# 08-1G_Phy2.net
KiCad netlist of a schematic drawn in Altium Designer
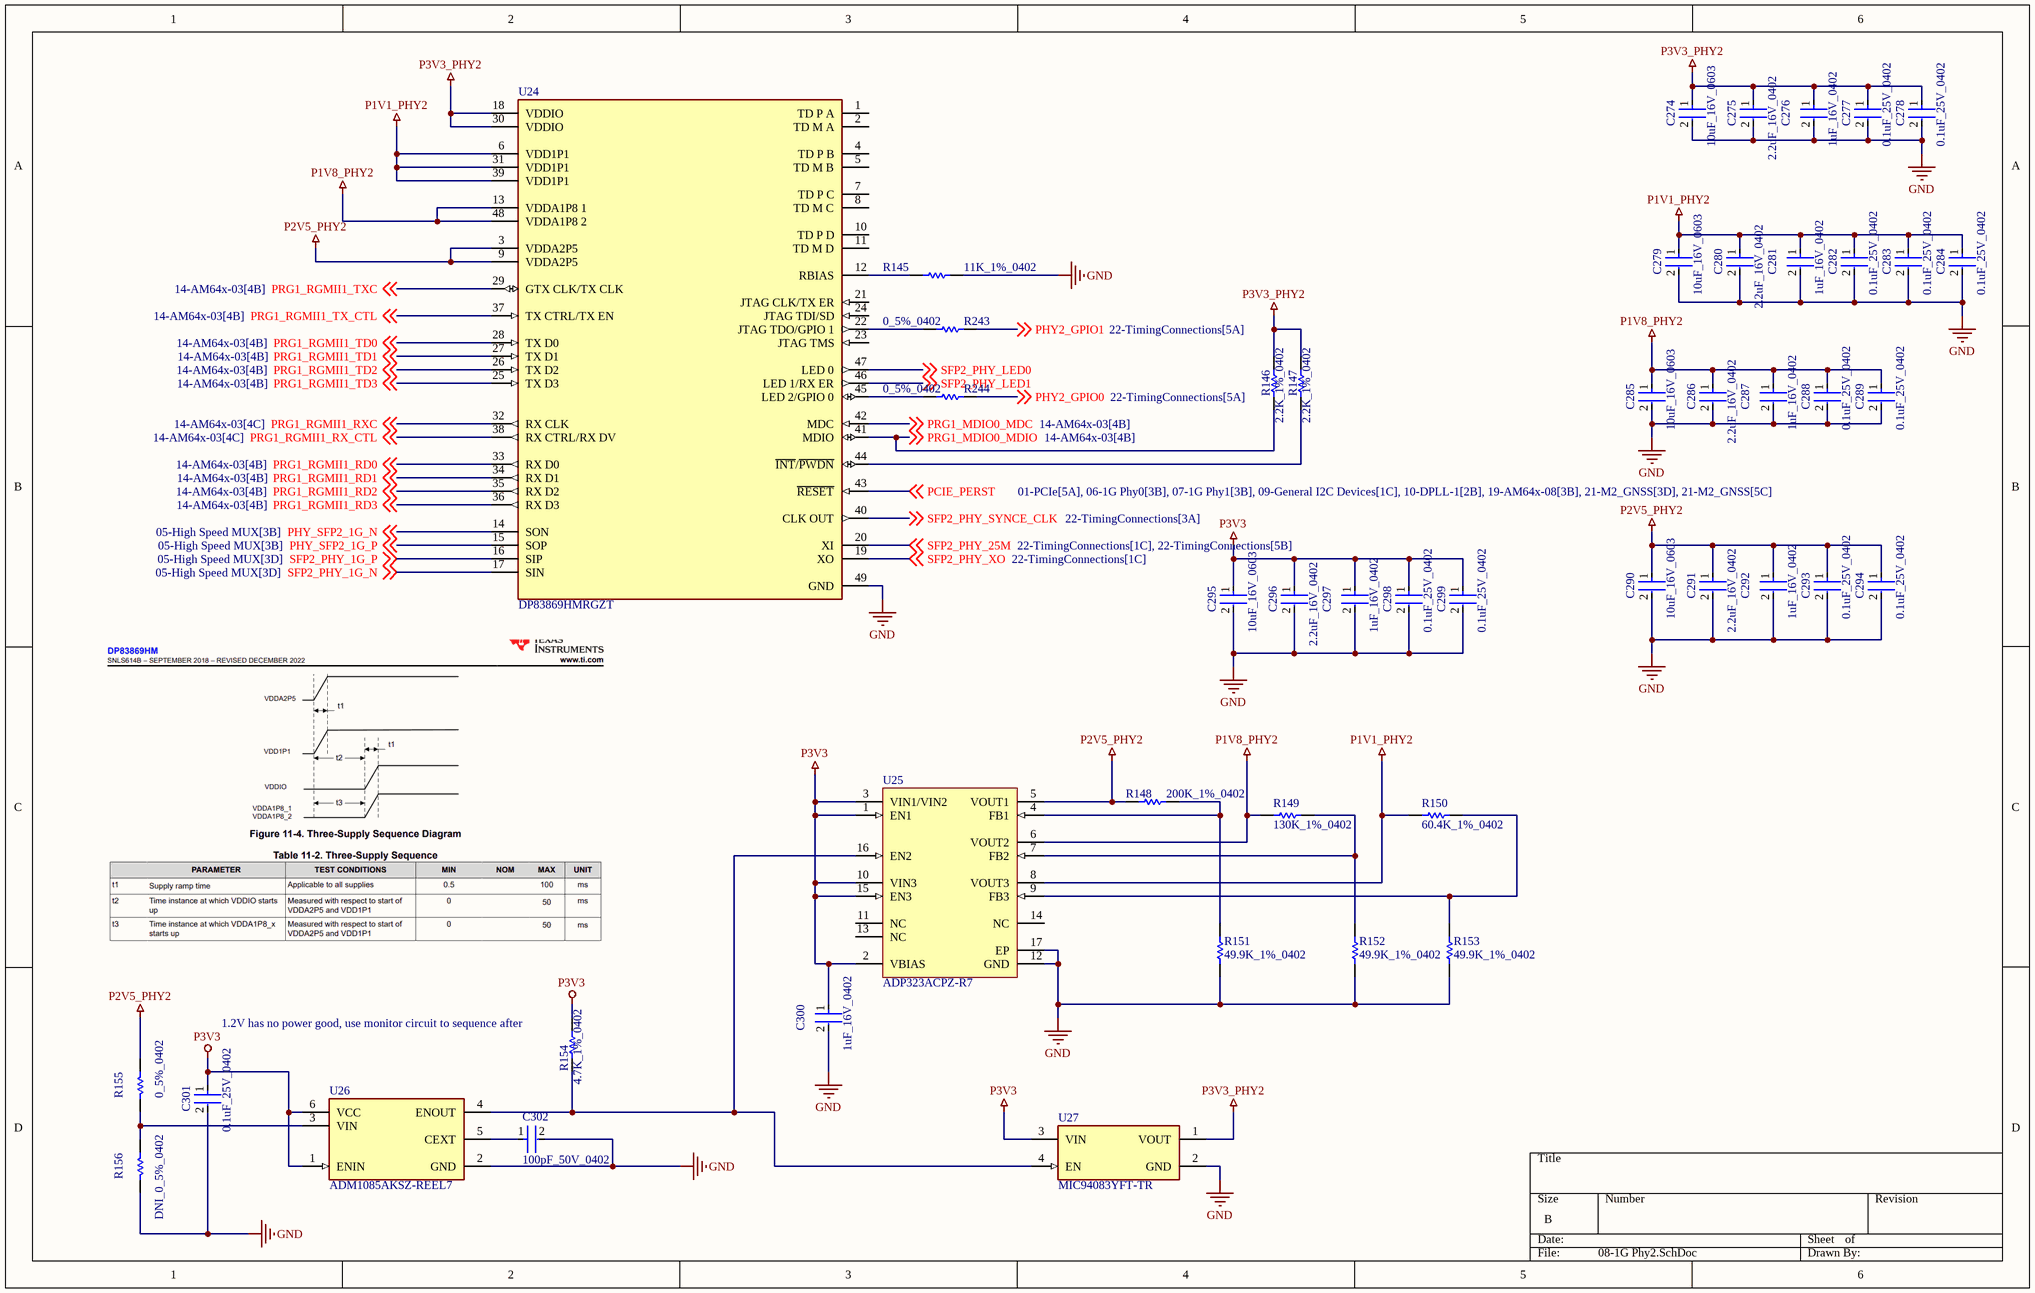
[diagram p0: 08-1G Phy2.SchDoc]

(export (version "E")
  (design (tool "Eeschema 10.0.6"))
  (components
    (comp (ref "C274")
      (value "10uF_16V_0603")
      (footprint "FP-0603-L_1_6_0_2-W_0_8_0-MFG")
      (description "Multilayer Ceramic Capacitor 10uF 16V X5R 20% SMD 0603 T/R")
      (fields (field (name "TOLERANCE") "20%"))
      (libsource (lib "Altium Content Vault") (part "b4654b650e69147ec39a6b967a45e02"))
    )
    (comp (ref "C275")
      (value "2.2uF_16V_0402")
      (footprint "FP-C1005-050-0_05-IPC_A")
      (description "Multilayer Ceramic Capacitors 2.2μF ±10% 16V X5R SMD 0402")
      (fields (field (name "TOLERANCE") "10%"))
      (libsource (lib "Altium Content Vault") (part "b4654b650e69147ec39a6b967a45e02"))
    )
    (comp (ref "C276")
      (value "1uF_16V_0402")
      (footprint "FP-0402-L_1_0_0_05-W_0_5-IPC_A")
      (description "None")
      (fields (field (name "TOLERANCE") "10%"))
      (libsource (lib "Altium Content Vault") (part "b4654b650e69147ec39a6b967a45e02"))
    )
    (comp (ref "C277")
      (value "0.1uF_25V_0402")
      (footprint "FP-0402-L_1_0_1-W_0_5_0_1-IPC_C")
      (description "General Purpose Ceramic Capacitor, 0402, 100nF, 10%, X7R, 15%, 25V")
      (fields (field (name "VOLTAGE") "25V") (field (name "TOLERANCE") "10%"))
      (libsource (lib "Altium Content Vault") (part "b4654b650e69147ec39a6b967a45e02"))
    )
    (comp (ref "C278")
      (value "0.1uF_25V_0402")
      (footprint "FP-0402-L_1_0_1-W_0_5_0_1-IPC_C")
      (description "General Purpose Ceramic Capacitor, 0402, 100nF, 10%, X7R, 15%, 25V")
      (fields (field (name "VOLTAGE") "25V") (field (name "TOLERANCE") "10%"))
      (libsource (lib "Altium Content Vault") (part "b4654b650e69147ec39a6b967a45e02"))
    )
    (comp (ref "C279")
      (value "10uF_16V_0603")
      (footprint "FP-0603-L_1_6_0_2-W_0_8_0-MFG")
      (description "Multilayer Ceramic Capacitor 10uF 16V X5R 20% SMD 0603 T/R")
      (fields (field (name "TOLERANCE") "20%"))
      (libsource (lib "Altium Content Vault") (part "b4654b650e69147ec39a6b967a45e02"))
    )
    (comp (ref "C280")
      (value "2.2uF_16V_0402")
      (footprint "FP-C1005-050-0_05-IPC_A")
      (description "Multilayer Ceramic Capacitors 2.2μF ±10% 16V X5R SMD 0402")
      (fields (field (name "TOLERANCE") "10%"))
      (libsource (lib "Altium Content Vault") (part "b4654b650e69147ec39a6b967a45e02"))
    )
    (comp (ref "C281")
      (value "1uF_16V_0402")
      (footprint "FP-0402-L_1_0_0_05-W_0_5-IPC_A")
      (description "None")
      (fields (field (name "TOLERANCE") "10%"))
      (libsource (lib "Altium Content Vault") (part "b4654b650e69147ec39a6b967a45e02"))
    )
    (comp (ref "C282")
      (value "0.1uF_25V_0402")
      (footprint "FP-0402-L_1_0_1-W_0_5_0_1-IPC_C")
      (description "General Purpose Ceramic Capacitor, 0402, 100nF, 10%, X7R, 15%, 25V")
      (fields (field (name "VOLTAGE") "25V") (field (name "TOLERANCE") "10%"))
      (libsource (lib "Altium Content Vault") (part "b4654b650e69147ec39a6b967a45e02"))
    )
    (comp (ref "C283")
      (value "0.1uF_25V_0402")
      (footprint "FP-0402-L_1_0_1-W_0_5_0_1-IPC_C")
      (description "General Purpose Ceramic Capacitor, 0402, 100nF, 10%, X7R, 15%, 25V")
      (fields (field (name "VOLTAGE") "25V") (field (name "TOLERANCE") "10%"))
      (libsource (lib "Altium Content Vault") (part "b4654b650e69147ec39a6b967a45e02"))
    )
    (comp (ref "C284")
      (value "0.1uF_25V_0402")
      (footprint "FP-0402-L_1_0_1-W_0_5_0_1-IPC_C")
      (description "General Purpose Ceramic Capacitor, 0402, 100nF, 10%, X7R, 15%, 25V")
      (fields (field (name "VOLTAGE") "25V") (field (name "TOLERANCE") "10%"))
      (libsource (lib "Altium Content Vault") (part "b4654b650e69147ec39a6b967a45e02"))
    )
    (comp (ref "C285")
      (value "10uF_16V_0603")
      (footprint "FP-0603-L_1_6_0_2-W_0_8_0-MFG")
      (description "Multilayer Ceramic Capacitor 10uF 16V X5R 20% SMD 0603 T/R")
      (fields (field (name "TOLERANCE") "20%"))
      (libsource (lib "Altium Content Vault") (part "b4654b650e69147ec39a6b967a45e02"))
    )
    (comp (ref "C286")
      (value "2.2uF_16V_0402")
      (footprint "FP-C1005-050-0_05-IPC_A")
      (description "Multilayer Ceramic Capacitors 2.2μF ±10% 16V X5R SMD 0402")
      (fields (field (name "TOLERANCE") "10%"))
      (libsource (lib "Altium Content Vault") (part "b4654b650e69147ec39a6b967a45e02"))
    )
    (comp (ref "C287")
      (value "1uF_16V_0402")
      (footprint "FP-0402-L_1_0_0_05-W_0_5-IPC_A")
      (description "None")
      (fields (field (name "TOLERANCE") "10%"))
      (libsource (lib "Altium Content Vault") (part "b4654b650e69147ec39a6b967a45e02"))
    )
    (comp (ref "C288")
      (value "0.1uF_25V_0402")
      (footprint "FP-0402-L_1_0_1-W_0_5_0_1-IPC_C")
      (description "General Purpose Ceramic Capacitor, 0402, 100nF, 10%, X7R, 15%, 25V")
      (fields (field (name "VOLTAGE") "25V") (field (name "TOLERANCE") "10%"))
      (libsource (lib "Altium Content Vault") (part "b4654b650e69147ec39a6b967a45e02"))
    )
    (comp (ref "C289")
      (value "0.1uF_25V_0402")
      (footprint "FP-0402-L_1_0_1-W_0_5_0_1-IPC_C")
      (description "General Purpose Ceramic Capacitor, 0402, 100nF, 10%, X7R, 15%, 25V")
      (fields (field (name "VOLTAGE") "25V") (field (name "TOLERANCE") "10%"))
      (libsource (lib "Altium Content Vault") (part "b4654b650e69147ec39a6b967a45e02"))
    )
    (comp (ref "C290")
      (value "10uF_16V_0603")
      (footprint "FP-0603-L_1_6_0_2-W_0_8_0-MFG")
      (description "Multilayer Ceramic Capacitor 10uF 16V X5R 20% SMD 0603 T/R")
      (fields (field (name "TOLERANCE") "20%"))
      (libsource (lib "Altium Content Vault") (part "b4654b650e69147ec39a6b967a45e02"))
    )
    (comp (ref "C291")
      (value "2.2uF_16V_0402")
      (footprint "FP-C1005-050-0_05-IPC_A")
      (description "Multilayer Ceramic Capacitors 2.2μF ±10% 16V X5R SMD 0402")
      (fields (field (name "TOLERANCE") "10%"))
      (libsource (lib "Altium Content Vault") (part "b4654b650e69147ec39a6b967a45e02"))
    )
    (comp (ref "C292")
      (value "1uF_16V_0402")
      (footprint "FP-0402-L_1_0_0_05-W_0_5-IPC_A")
      (description "None")
      (fields (field (name "TOLERANCE") "10%"))
      (libsource (lib "Altium Content Vault") (part "b4654b650e69147ec39a6b967a45e02"))
    )
    (comp (ref "C293")
      (value "0.1uF_25V_0402")
      (footprint "FP-0402-L_1_0_1-W_0_5_0_1-IPC_C")
      (description "General Purpose Ceramic Capacitor, 0402, 100nF, 10%, X7R, 15%, 25V")
      (fields (field (name "VOLTAGE") "25V") (field (name "TOLERANCE") "10%"))
      (libsource (lib "Altium Content Vault") (part "b4654b650e69147ec39a6b967a45e02"))
    )
    (comp (ref "C294")
      (value "0.1uF_25V_0402")
      (footprint "FP-0402-L_1_0_1-W_0_5_0_1-IPC_C")
      (description "General Purpose Ceramic Capacitor, 0402, 100nF, 10%, X7R, 15%, 25V")
      (fields (field (name "VOLTAGE") "25V") (field (name "TOLERANCE") "10%"))
      (libsource (lib "Altium Content Vault") (part "b4654b650e69147ec39a6b967a45e02"))
    )
    (comp (ref "C295")
      (value "10uF_16V_0603")
      (footprint "FP-0603-L_1_6_0_2-W_0_8_0-MFG")
      (description "Multilayer Ceramic Capacitor 10uF 16V X5R 20% SMD 0603 T/R")
      (fields (field (name "TOLERANCE") "20%"))
      (libsource (lib "Altium Content Vault") (part "b4654b650e69147ec39a6b967a45e02"))
    )
    (comp (ref "C296")
      (value "2.2uF_16V_0402")
      (footprint "FP-C1005-050-0_05-IPC_A")
      (description "Multilayer Ceramic Capacitors 2.2μF ±10% 16V X5R SMD 0402")
      (fields (field (name "TOLERANCE") "10%"))
      (libsource (lib "Altium Content Vault") (part "b4654b650e69147ec39a6b967a45e02"))
    )
    (comp (ref "C297")
      (value "1uF_16V_0402")
      (footprint "FP-0402-L_1_0_0_05-W_0_5-IPC_A")
      (description "None")
      (fields (field (name "TOLERANCE") "10%"))
      (libsource (lib "Altium Content Vault") (part "b4654b650e69147ec39a6b967a45e02"))
    )
    (comp (ref "C298")
      (value "0.1uF_25V_0402")
      (footprint "FP-0402-L_1_0_1-W_0_5_0_1-IPC_C")
      (description "General Purpose Ceramic Capacitor, 0402, 100nF, 10%, X7R, 15%, 25V")
      (fields (field (name "VOLTAGE") "25V") (field (name "TOLERANCE") "10%"))
      (libsource (lib "Altium Content Vault") (part "b4654b650e69147ec39a6b967a45e02"))
    )
    (comp (ref "C299")
      (value "0.1uF_25V_0402")
      (footprint "FP-0402-L_1_0_1-W_0_5_0_1-IPC_C")
      (description "General Purpose Ceramic Capacitor, 0402, 100nF, 10%, X7R, 15%, 25V")
      (fields (field (name "VOLTAGE") "25V") (field (name "TOLERANCE") "10%"))
      (libsource (lib "Altium Content Vault") (part "b4654b650e69147ec39a6b967a45e02"))
    )
    (comp (ref "C300")
      (value "1uF_16V_0402")
      (footprint "FP-0402-L_1_0_0_05-W_0_5-IPC_A")
      (description "None")
      (fields (field (name "TOLERANCE") "10%"))
      (libsource (lib "Altium Content Vault") (part "b4654b650e69147ec39a6b967a45e02"))
    )
    (comp (ref "C301")
      (value "0.1uF_25V_0402")
      (footprint "FP-0402-L_1_0_1-W_0_5_0_1-IPC_C")
      (description "General Purpose Ceramic Capacitor, 0402, 100nF, 10%, X7R, 15%, 25V")
      (fields (field (name "VOLTAGE") "25V") (field (name "TOLERANCE") "10%"))
      (libsource (lib "Altium Content Vault") (part "b4654b650e69147ec39a6b967a45e02"))
    )
    (comp (ref "C302")
      (value "100pF_50V_0402")
      (footprint "FP-C0402-BB-MFG")
      (description "CAP CER 100PF 50V C0G/NP0 0402")
      (fields (field (name "TOLERANCE") "0.02") (field (name "MANUFACTURER") "Kemet"))
      (libsource (lib "Altium Content Vault") (part "b4654b650e69147ec39a6b967a45e02"))
    )
    (comp (ref "R145")
      (value "11K_1%_0402")
      (footprint "RESC1005X40X25LL05T10")
      (fields (field (name "MANUFACTURER") "Yageo / Phycomp") (field (name "PART NUMBER") "RC0402FR-0711KL"))
      (libsource (lib "Altium Content Vault") (part "RES"))
    )
    (comp (ref "R146")
      (value "2.2K_1%_0402")
      (footprint "RESC1005X40X25ML10T10")
      (fields (field (name "PART NUMBER") "MC00625W040212K2") (field (name "MANUFACTURER") "Multicomp"))
      (libsource (lib "Altium Content Vault") (part "RES"))
    )
    (comp (ref "R147")
      (value "2.2K_1%_0402")
      (footprint "RESC1005X40X25ML10T10")
      (fields (field (name "PART NUMBER") "MC00625W040212K2") (field (name "MANUFACTURER") "Multicomp"))
      (libsource (lib "Altium Content Vault") (part "RES"))
    )
    (comp (ref "R148")
      (value "200K_1%_0402")
      (footprint "RESC1005X40X25LL10T10")
      (fields (field (name "PART NUMBER") "CR0402-FX-2003GLF") (field (name "MANUFACTURER") "Bourns"))
      (libsource (lib "Altium Content Vault") (part "RES"))
    )
    (comp (ref "R149")
      (value "130K_1%_0402")
      (footprint "RESC1005X40X25NL10T10")
      (fields
        (field (name "PART NUMBER") "CRG0402F130K")
        (field (name "MANUFACTURER") "TE Connectivity / AMP")
      )
      (libsource (lib "Altium Content Vault") (part "RES"))
    )
    (comp (ref "R150")
      (value "60.4K_1%_0402")
      (footprint "RESC1005X40X25LL05T10")
      (fields (field (name "MANUFACTURER") "Yageo / Phycomp") (field (name "PART NUMBER") "RC0402FR-0760K4L"))
      (libsource (lib "Altium Content Vault") (part "RES"))
    )
    (comp (ref "R151")
      (value "49.9K_1%_0402")
      (footprint "RESC1005X40X25LL10T10")
      (fields (field (name "MANUFACTURER") "Bourns") (field (name "PART NUMBER") "CR0402-FX-4992GLF"))
      (libsource (lib "Altium Content Vault") (part "RES"))
    )
    (comp (ref "R152")
      (value "49.9K_1%_0402")
      (footprint "RESC1005X40X25LL10T10")
      (fields (field (name "MANUFACTURER") "Bourns") (field (name "PART NUMBER") "CR0402-FX-4992GLF"))
      (libsource (lib "Altium Content Vault") (part "RES"))
    )
    (comp (ref "R153")
      (value "49.9K_1%_0402")
      (footprint "RESC1005X40X25LL10T10")
      (fields (field (name "MANUFACTURER") "Bourns") (field (name "PART NUMBER") "CR0402-FX-4992GLF"))
      (libsource (lib "Altium Content Vault") (part "RES"))
    )
    (comp (ref "R154")
      (value "4.7K_1%_0402")
      (footprint "RESC1005X40X25NL10T10")
      (fields (field (name "MANUFACTURER") "Bourns") (field (name "PART NUMBER") "CR0402-FX-4701GLF"))
      (libsource (lib "Altium Content Vault") (part "RES"))
    )
    (comp (ref "R155")
      (value "0_5%_0402")
      (footprint "RESC1005X40X25LL10T10")
      (fields (field (name "MANUFACTURER") "KOA Speer") (field (name "PART NUMBER") "RK73Z1ETTP"))
      (libsource (lib "Altium Content Vault") (part "RES"))
    )
    (comp (ref "R156")
      (value "DNI_0_5%_0402")
      (footprint "RESC1005X40X25LL10T10")
      (fields (field (name "MANUFACTURER") "KOA Speer") (field (name "PART NUMBER") "RK73Z1ETTP"))
      (libsource (lib "Altium Content Vault") (part "RES"))
    )
    (comp (ref "R243")
      (value "0_5%_0402")
      (footprint "RESC1005X40X25LL10T10")
      (fields (field (name "MANUFACTURER") "KOA Speer") (field (name "PART NUMBER") "RK73Z1ETTP"))
      (libsource (lib "Altium Content Vault") (part "RES"))
    )
    (comp (ref "R244")
      (value "0_5%_0402")
      (footprint "RESC1005X40X25LL10T10")
      (fields (field (name "MANUFACTURER") "KOA Speer") (field (name "PART NUMBER") "RK73Z1ETTP"))
      (libsource (lib "Altium Content Vault") (part "RES"))
    )
    (comp (ref "U24")
      (value "DP83869HMRGZT")
      (footprint "FP-RGZ0048B-IPC_A")
      (description "IC TRANSCEIVER 1/1 48FN")
      (libsource (lib "Altium Content Vault") (part "90cc30aaca705ff2adc2433a1cc0005"))
    )
    (comp (ref "U25")
      (value "ADP323ACPZ-R7")
      (footprint "ADI-CP-16-27_N")
      (fields (field (name "MANUFACTURER") "Analog Devices"))
      (libsource (lib "Altium Content Vault") (part "ADI-ADP323-CP-16-27"))
    )
    (comp (ref "U26")
      (value "ADM1085AKSZ-REEL7")
      (footprint "FP-KS-6-IPC_B")
      (description "IC SUPERVISOR 1 CHANNEL SC70-6")
      (libsource (lib "Altium Content Vault") (part "4d0b74b7e8e8a1541abc8f47282371d"))
    )
    (comp (ref "U27")
      (value "MIC94083YFT-TR")
      (footprint "FP-FTDFN085085-4LD-PL-1-MFG")
      (description "IC PWR SWITCH P-CHAN 1:1 4TMLF")
      (libsource (lib "Altium Content Vault") (part "f982b0e4379ad1be1c154354d61e319"))
    )
  )
  (nets
    (net (code "1") (name "GND") (class "Default")
      (node (ref "C274") (pin "2") (pinfunction "2_2") (pintype "passive"))
      (node (ref "C275") (pin "2") (pinfunction "2_2") (pintype "passive"))
      (node (ref "C276") (pin "2") (pinfunction "2_2") (pintype "passive"))
      (node (ref "C277") (pin "2") (pinfunction "2_2") (pintype "passive"))
      (node (ref "C278") (pin "2") (pinfunction "2_2") (pintype "passive"))
      (node (ref "C279") (pin "2") (pinfunction "2_2") (pintype "passive"))
      (node (ref "C280") (pin "2") (pinfunction "2_2") (pintype "passive"))
      (node (ref "C281") (pin "2") (pinfunction "2_2") (pintype "passive"))
      (node (ref "C282") (pin "2") (pinfunction "2_2") (pintype "passive"))
      (node (ref "C283") (pin "2") (pinfunction "2_2") (pintype "passive"))
      (node (ref "C284") (pin "2") (pinfunction "2_2") (pintype "passive"))
      (node (ref "C285") (pin "2") (pinfunction "2_2") (pintype "passive"))
      (node (ref "C286") (pin "2") (pinfunction "2_2") (pintype "passive"))
      (node (ref "C287") (pin "2") (pinfunction "2_2") (pintype "passive"))
      (node (ref "C288") (pin "2") (pinfunction "2_2") (pintype "passive"))
      (node (ref "C289") (pin "2") (pinfunction "2_2") (pintype "passive"))
      (node (ref "C290") (pin "2") (pinfunction "2_2") (pintype "passive"))
      (node (ref "C291") (pin "2") (pinfunction "2_2") (pintype "passive"))
      (node (ref "C292") (pin "2") (pinfunction "2_2") (pintype "passive"))
      (node (ref "C293") (pin "2") (pinfunction "2_2") (pintype "passive"))
      (node (ref "C294") (pin "2") (pinfunction "2_2") (pintype "passive"))
      (node (ref "C295") (pin "2") (pinfunction "2_2") (pintype "passive"))
      (node (ref "C296") (pin "2") (pinfunction "2_2") (pintype "passive"))
      (node (ref "C297") (pin "2") (pinfunction "2_2") (pintype "passive"))
      (node (ref "C298") (pin "2") (pinfunction "2_2") (pintype "passive"))
      (node (ref "C299") (pin "2") (pinfunction "2_2") (pintype "passive"))
      (node (ref "C300") (pin "2") (pinfunction "2_2") (pintype "passive"))
      (node (ref "C301") (pin "2") (pinfunction "2_2") (pintype "passive"))
      (node (ref "C302") (pin "2") (pinfunction "2_2") (pintype "passive"))
      (node (ref "R145") (pin "2") (pinfunction "2_2") (pintype "passive"))
      (node (ref "R151") (pin "1") (pinfunction "1_1") (pintype "passive"))
      (node (ref "R152") (pin "1") (pinfunction "1_1") (pintype "passive"))
      (node (ref "R153") (pin "1") (pinfunction "1_1") (pintype "passive"))
      (node (ref "R156") (pin "2") (pinfunction "2_2") (pintype "passive"))
      (node (ref "U24") (pin "49") (pinfunction "GND_49") (pintype "power_in"))
      (node (ref "U25") (pin "12") (pinfunction "GND_12") (pintype "power_in"))
      (node (ref "U25") (pin "17") (pinfunction "EP_17") (pintype "power_in"))
      (node (ref "U26") (pin "2") (pinfunction "GND_2") (pintype "power_in"))
      (node (ref "U27") (pin "2") (pinfunction "GND_2") (pintype "power_in"))
    )
    (net (code "2") (name "Net-(U24-JTAG_TDO{slash}GPIO_1)") (class "Default")
      (node (ref "R243") (pin "1") (pinfunction "1_1") (pintype "passive"))
      (node (ref "U24") (pin "22") (pinfunction "JTAG_TDO/GPIO_1_22") (pintype "output"))
    )
    (net (code "3") (name "Net-(U24-LED_2{slash}GPIO_0)") (class "Default")
      (node (ref "R244") (pin "1") (pinfunction "1_1") (pintype "passive"))
      (node (ref "U24") (pin "45") (pinfunction "LED_2/GPIO_0_45") (pintype "bidirectional"))
    )
    (net (code "4") (name "Net-(U24-RBIAS)") (class "Default")
      (node (ref "R145") (pin "1") (pinfunction "1_1") (pintype "passive"))
      (node (ref "U24") (pin "12") (pinfunction "RBIAS_12") (pintype "passive"))
    )
    (net (code "5") (name "Net-(U24-~{INT}{slash}~{PWDN})") (class "Default")
      (node (ref "R147") (pin "1") (pinfunction "1_1") (pintype "passive"))
      (node (ref "U24") (pin "44") (pinfunction "~{INT}/~{PWDN}_44") (pintype "bidirectional"))
    )
    (net (code "6") (name "Net-(U25-EN2)") (class "Default")
      (node (ref "R154") (pin "2") (pinfunction "2_2") (pintype "passive"))
      (node (ref "U25") (pin "16") (pinfunction "EN2_16") (pintype "input"))
      (node (ref "U26") (pin "4") (pinfunction "ENOUT_4") (pintype "open_collector"))
      (node (ref "U27") (pin "4") (pinfunction "EN_4") (pintype "input"))
    )
    (net (code "7") (name "Net-(U25-FB1)") (class "Default")
      (node (ref "R148") (pin "2") (pinfunction "2_2") (pintype "passive"))
      (node (ref "R151") (pin "2") (pinfunction "2_2") (pintype "passive"))
      (node (ref "U25") (pin "4") (pinfunction "FB1_4") (pintype "input"))
    )
    (net (code "8") (name "Net-(U25-FB2)") (class "Default")
      (node (ref "R149") (pin "2") (pinfunction "2_2") (pintype "passive"))
      (node (ref "R152") (pin "2") (pinfunction "2_2") (pintype "passive"))
      (node (ref "U25") (pin "7") (pinfunction "FB2_7") (pintype "input"))
    )
    (net (code "9") (name "Net-(U25-FB3)") (class "Default")
      (node (ref "R150") (pin "2") (pinfunction "2_2") (pintype "passive"))
      (node (ref "R153") (pin "2") (pinfunction "2_2") (pintype "passive"))
      (node (ref "U25") (pin "9") (pinfunction "FB3_9") (pintype "input"))
    )
    (net (code "10") (name "Net-(U26-CEXT)") (class "Default")
      (node (ref "C302") (pin "1") (pinfunction "1_1") (pintype "passive"))
      (node (ref "U26") (pin "5") (pinfunction "CEXT_5") (pintype "passive"))
    )
    (net (code "11") (name "Net-(U26-VIN)") (class "Default")
      (node (ref "R155") (pin "2") (pinfunction "2_2") (pintype "passive"))
      (node (ref "R156") (pin "1") (pinfunction "1_1") (pintype "passive"))
      (node (ref "U26") (pin "3") (pinfunction "VIN_3") (pintype "power_in"))
    )
    (net (code "12") (name "P1V1_PHY2") (class "Default")
      (node (ref "C279") (pin "1") (pinfunction "1_1") (pintype "passive"))
      (node (ref "C280") (pin "1") (pinfunction "1_1") (pintype "passive"))
      (node (ref "C281") (pin "1") (pinfunction "1_1") (pintype "passive"))
      (node (ref "C282") (pin "1") (pinfunction "1_1") (pintype "passive"))
      (node (ref "C283") (pin "1") (pinfunction "1_1") (pintype "passive"))
      (node (ref "C284") (pin "1") (pinfunction "1_1") (pintype "passive"))
      (node (ref "R150") (pin "1") (pinfunction "1_1") (pintype "passive"))
      (node (ref "U24") (pin "31") (pinfunction "VDD1P1_31") (pintype "power_in"))
      (node (ref "U24") (pin "39") (pinfunction "VDD1P1_39") (pintype "power_in"))
      (node (ref "U24") (pin "6") (pinfunction "VDD1P1_6") (pintype "power_in"))
      (node (ref "U25") (pin "8") (pinfunction "VOUT3_8") (pintype "power_in"))
    )
    (net (code "13") (name "P1V8_PHY2") (class "Default")
      (node (ref "C285") (pin "1") (pinfunction "1_1") (pintype "passive"))
      (node (ref "C286") (pin "1") (pinfunction "1_1") (pintype "passive"))
      (node (ref "C287") (pin "1") (pinfunction "1_1") (pintype "passive"))
      (node (ref "C288") (pin "1") (pinfunction "1_1") (pintype "passive"))
      (node (ref "C289") (pin "1") (pinfunction "1_1") (pintype "passive"))
      (node (ref "R149") (pin "1") (pinfunction "1_1") (pintype "passive"))
      (node (ref "U24") (pin "13") (pinfunction "VDDA1P8_1_13") (pintype "power_in"))
      (node (ref "U24") (pin "48") (pinfunction "VDDA1P8_2_48") (pintype "power_in"))
      (node (ref "U25") (pin "6") (pinfunction "VOUT2_6") (pintype "power_in"))
    )
    (net (code "14") (name "P2V5_PHY2") (class "Default")
      (node (ref "C290") (pin "1") (pinfunction "1_1") (pintype "passive"))
      (node (ref "C291") (pin "1") (pinfunction "1_1") (pintype "passive"))
      (node (ref "C292") (pin "1") (pinfunction "1_1") (pintype "passive"))
      (node (ref "C293") (pin "1") (pinfunction "1_1") (pintype "passive"))
      (node (ref "C294") (pin "1") (pinfunction "1_1") (pintype "passive"))
      (node (ref "R148") (pin "1") (pinfunction "1_1") (pintype "passive"))
      (node (ref "R155") (pin "1") (pinfunction "1_1") (pintype "passive"))
      (node (ref "U24") (pin "3") (pinfunction "VDDA2P5_3") (pintype "power_in"))
      (node (ref "U24") (pin "9") (pinfunction "VDDA2P5_9") (pintype "power_in"))
      (node (ref "U25") (pin "5") (pinfunction "VOUT1_5") (pintype "power_in"))
    )
    (net (code "15") (name "P3V3") (class "Default")
      (node (ref "C295") (pin "1") (pinfunction "1_1") (pintype "passive"))
      (node (ref "C296") (pin "1") (pinfunction "1_1") (pintype "passive"))
      (node (ref "C297") (pin "1") (pinfunction "1_1") (pintype "passive"))
      (node (ref "C298") (pin "1") (pinfunction "1_1") (pintype "passive"))
      (node (ref "C299") (pin "1") (pinfunction "1_1") (pintype "passive"))
      (node (ref "C300") (pin "1") (pinfunction "1_1") (pintype "passive"))
      (node (ref "C301") (pin "1") (pinfunction "1_1") (pintype "passive"))
      (node (ref "R154") (pin "1") (pinfunction "1_1") (pintype "passive"))
      (node (ref "U25") (pin "1") (pinfunction "EN1_1") (pintype "input"))
      (node (ref "U25") (pin "10") (pinfunction "VIN3_10") (pintype "power_in"))
      (node (ref "U25") (pin "15") (pinfunction "EN3_15") (pintype "input"))
      (node (ref "U25") (pin "2") (pinfunction "VBIAS_2") (pintype "power_in"))
      (node (ref "U25") (pin "3") (pinfunction "VIN1/VIN2_3") (pintype "power_in"))
      (node (ref "U26") (pin "1") (pinfunction "ENIN_1") (pintype "input"))
      (node (ref "U26") (pin "6") (pinfunction "VCC_6") (pintype "power_in"))
      (node (ref "U27") (pin "3") (pinfunction "VIN_3") (pintype "power_in"))
    )
    (net (code "16") (name "P3V3_PHY2") (class "Default")
      (node (ref "C274") (pin "1") (pinfunction "1_1") (pintype "passive"))
      (node (ref "C275") (pin "1") (pinfunction "1_1") (pintype "passive"))
      (node (ref "C276") (pin "1") (pinfunction "1_1") (pintype "passive"))
      (node (ref "C277") (pin "1") (pinfunction "1_1") (pintype "passive"))
      (node (ref "C278") (pin "1") (pinfunction "1_1") (pintype "passive"))
      (node (ref "R146") (pin "2") (pinfunction "2_2") (pintype "passive"))
      (node (ref "R147") (pin "2") (pinfunction "2_2") (pintype "passive"))
      (node (ref "U24") (pin "18") (pinfunction "VDDIO_18") (pintype "power_in"))
      (node (ref "U24") (pin "30") (pinfunction "VDDIO_30") (pintype "power_in"))
      (node (ref "U27") (pin "1") (pinfunction "VOUT_1") (pintype "power_in"))
    )
    (net (code "17") (name "PCIE_PERST") (class "Default")
      (node (ref "U24") (pin "43") (pinfunction "~{RESET}_43") (pintype "input"))
    )
    (net (code "18") (name "PHY2_GPIO0") (class "Default")
      (node (ref "R244") (pin "2") (pinfunction "2_2") (pintype "passive"))
    )
    (net (code "19") (name "PHY2_GPIO1") (class "Default")
      (node (ref "R243") (pin "2") (pinfunction "2_2") (pintype "passive"))
    )
    (net (code "20") (name "PHY_SFP2_1G_N") (class "Default")
      (node (ref "U24") (pin "14") (pinfunction "SON_14") (pintype "passive"))
    )
    (net (code "21") (name "PHY_SFP2_1G_P") (class "Default")
      (node (ref "U24") (pin "15") (pinfunction "SOP_15") (pintype "passive"))
    )
    (net (code "22") (name "PRG1_MDIO0_MDC") (class "Default")
      (node (ref "U24") (pin "42") (pinfunction "MDC_42") (pintype "input"))
    )
    (net (code "23") (name "PRG1_MDIO0_MDIO") (class "Default")
      (node (ref "R146") (pin "1") (pinfunction "1_1") (pintype "passive"))
      (node (ref "U24") (pin "41") (pinfunction "MDIO_41") (pintype "bidirectional"))
    )
    (net (code "24") (name "PRG1_RGMII1_RD0") (class "Default")
      (node (ref "U24") (pin "33") (pinfunction "RX_D0_33") (pintype "output"))
    )
    (net (code "25") (name "PRG1_RGMII1_RD1") (class "Default")
      (node (ref "U24") (pin "34") (pinfunction "RX_D1_34") (pintype "output"))
    )
    (net (code "26") (name "PRG1_RGMII1_RD2") (class "Default")
      (node (ref "U24") (pin "35") (pinfunction "RX_D2_35") (pintype "output"))
    )
    (net (code "27") (name "PRG1_RGMII1_RD3") (class "Default")
      (node (ref "U24") (pin "36") (pinfunction "RX_D3_36") (pintype "output"))
    )
    (net (code "28") (name "PRG1_RGMII1_RXC") (class "Default")
      (node (ref "U24") (pin "32") (pinfunction "RX_CLK_32") (pintype "output"))
    )
    (net (code "29") (name "PRG1_RGMII1_RX_CTL") (class "Default")
      (node (ref "U24") (pin "38") (pinfunction "RX_CTRL/RX_DV_38") (pintype "output"))
    )
    (net (code "30") (name "PRG1_RGMII1_TD0") (class "Default")
      (node (ref "U24") (pin "28") (pinfunction "TX_D0_28") (pintype "input"))
    )
    (net (code "31") (name "PRG1_RGMII1_TD1") (class "Default")
      (node (ref "U24") (pin "27") (pinfunction "TX_D1_27") (pintype "input"))
    )
    (net (code "32") (name "PRG1_RGMII1_TD2") (class "Default")
      (node (ref "U24") (pin "26") (pinfunction "TX_D2_26") (pintype "input"))
    )
    (net (code "33") (name "PRG1_RGMII1_TD3") (class "Default")
      (node (ref "U24") (pin "25") (pinfunction "TX_D3_25") (pintype "input"))
    )
    (net (code "34") (name "PRG1_RGMII1_TXC") (class "Default")
      (node (ref "U24") (pin "29") (pinfunction "GTX_CLK/TX_CLK_29") (pintype "bidirectional"))
    )
    (net (code "35") (name "PRG1_RGMII1_TX_CTL") (class "Default")
      (node (ref "U24") (pin "37") (pinfunction "TX_CTRL/TX_EN_37") (pintype "input"))
    )
    (net (code "36") (name "SFP2_PHY_1G_N") (class "Default")
      (node (ref "U24") (pin "17") (pinfunction "SIN_17") (pintype "passive"))
    )
    (net (code "37") (name "SFP2_PHY_1G_P") (class "Default")
      (node (ref "U24") (pin "16") (pinfunction "SIP_16") (pintype "passive"))
    )
    (net (code "38") (name "SFP2_PHY_25M") (class "Default")
      (node (ref "U24") (pin "20") (pinfunction "XI_20") (pintype "passive"))
    )
    (net (code "39") (name "SFP2_PHY_LED0") (class "Default")
      (node (ref "U24") (pin "47") (pinfunction "LED_0_47") (pintype "output"))
    )
    (net (code "40") (name "SFP2_PHY_LED1") (class "Default")
      (node (ref "U24") (pin "46") (pinfunction "LED_1/RX_ER_46") (pintype "output"))
    )
    (net (code "41") (name "SFP2_PHY_SYNCE_CLK") (class "Default")
      (node (ref "U24") (pin "40") (pinfunction "CLK_OUT_40") (pintype "output"))
    )
    (net (code "42") (name "SFP2_PHY_XO") (class "Default")
      (node (ref "U24") (pin "19") (pinfunction "XO_19") (pintype "passive"))
    )
    (net (code "43") (name "unconnected-(U24-JTAG_CLK{slash}TX_ER-Pad21)") (class "Default")
      (node (ref "U24") (pin "21") (pinfunction "JTAG_CLK/TX_ER_21") (pintype "input"))
    )
    (net (code "44") (name "unconnected-(U24-JTAG_TDI{slash}SD-Pad24)") (class "Default")
      (node (ref "U24") (pin "24") (pinfunction "JTAG_TDI/SD_24") (pintype "input"))
    )
    (net (code "45") (name "unconnected-(U24-JTAG_TMS-Pad23)") (class "Default")
      (node (ref "U24") (pin "23") (pinfunction "JTAG_TMS_23") (pintype "input"))
    )
    (net (code "46") (name "unconnected-(U24-TD_M_A-Pad2)") (class "Default")
      (node (ref "U24") (pin "2") (pinfunction "TD_M_A_2") (pintype "passive"))
    )
    (net (code "47") (name "unconnected-(U24-TD_M_B-Pad5)") (class "Default")
      (node (ref "U24") (pin "5") (pinfunction "TD_M_B_5") (pintype "passive"))
    )
    (net (code "48") (name "unconnected-(U24-TD_M_C-Pad8)") (class "Default")
      (node (ref "U24") (pin "8") (pinfunction "TD_M_C_8") (pintype "passive"))
    )
    (net (code "49") (name "unconnected-(U24-TD_M_D-Pad11)") (class "Default")
      (node (ref "U24") (pin "11") (pinfunction "TD_M_D_11") (pintype "passive"))
    )
    (net (code "50") (name "unconnected-(U24-TD_P_A-Pad1)") (class "Default")
      (node (ref "U24") (pin "1") (pinfunction "TD_P_A_1") (pintype "passive"))
    )
    (net (code "51") (name "unconnected-(U24-TD_P_B-Pad4)") (class "Default")
      (node (ref "U24") (pin "4") (pinfunction "TD_P_B_4") (pintype "passive"))
    )
    (net (code "52") (name "unconnected-(U24-TD_P_C-Pad7)") (class "Default")
      (node (ref "U24") (pin "7") (pinfunction "TD_P_C_7") (pintype "passive"))
    )
    (net (code "53") (name "unconnected-(U24-TD_P_D-Pad10)") (class "Default")
      (node (ref "U24") (pin "10") (pinfunction "TD_P_D_10") (pintype "passive"))
    )
    (net (code "54") (name "unconnected-(U25-NC-Pad11)") (class "Default")
      (node (ref "U25") (pin "11") (pinfunction "NC_11") (pintype "passive"))
    )
    (net (code "55") (name "unconnected-(U25-NC-Pad13)") (class "Default")
      (node (ref "U25") (pin "13") (pinfunction "NC_13") (pintype "passive"))
    )
    (net (code "56") (name "unconnected-(U25-NC-Pad14)") (class "Default")
      (node (ref "U25") (pin "14") (pinfunction "NC_14") (pintype "passive"))
    )
  )
)
